# SMPS_power_supply.net
KiCad netlist of a schematic drawn in Altium Designer
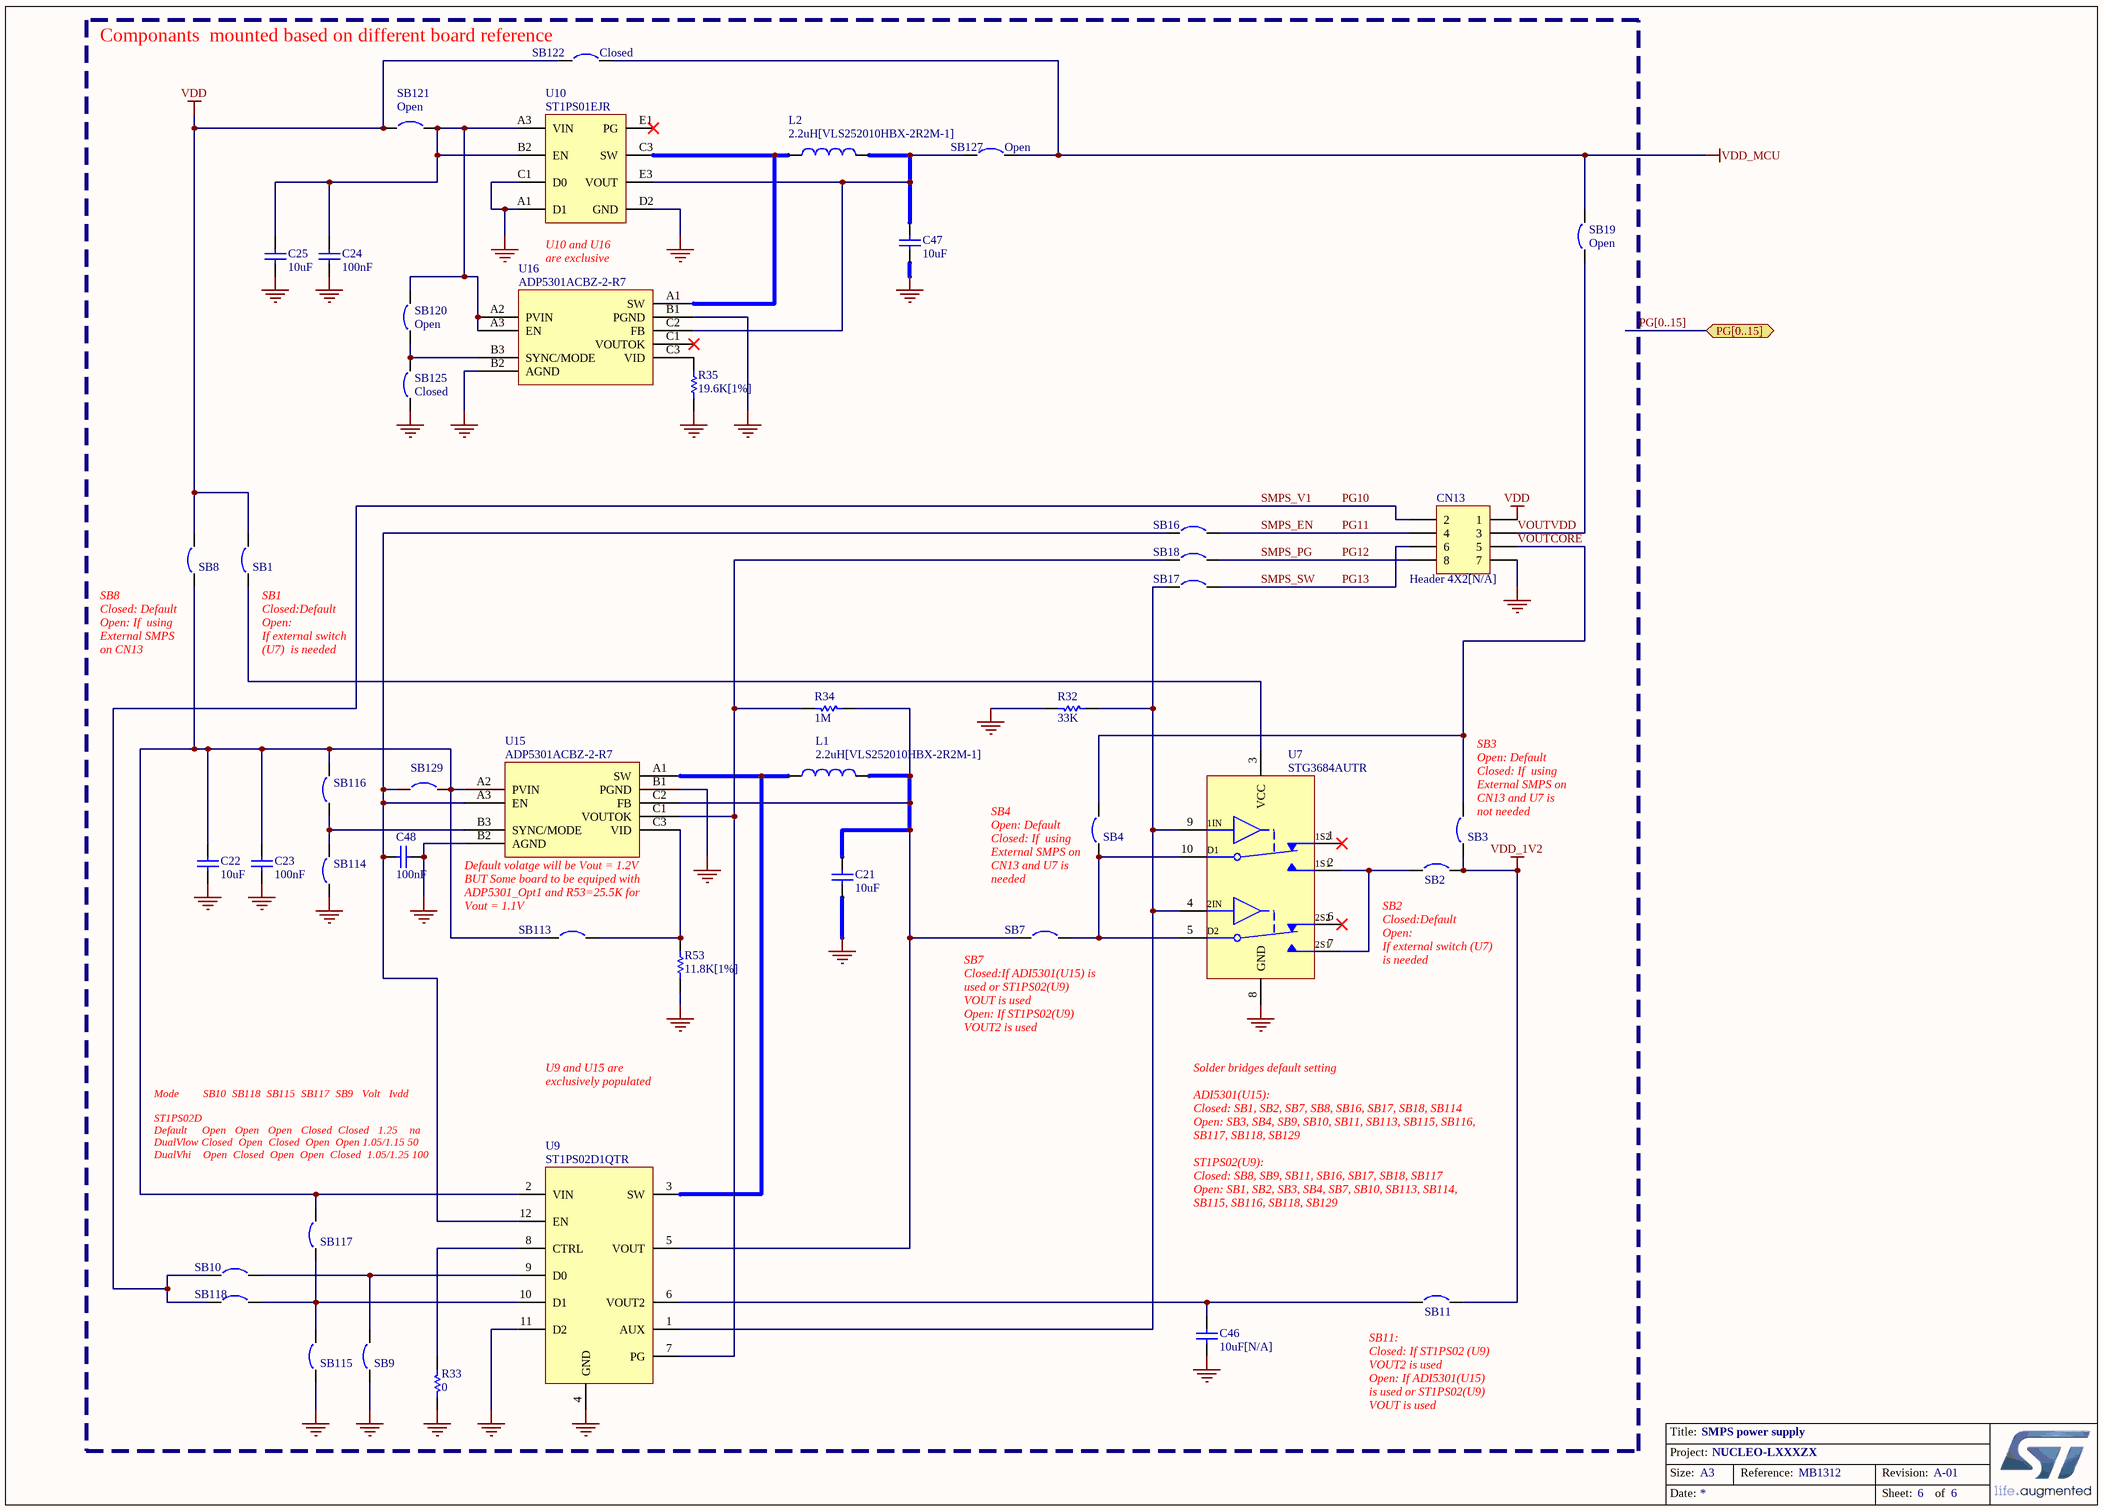
[diagram p0: SMPS power supply.SchDoc]

(export (version "E")
  (design (tool "Eeschema 10.0.6"))
  (components
    (comp (ref "C21")
      (value "10uF")
      (footprint "0603C")
      (description "Capacitor")
      (fields (field (name "PUBLISHER") "Altium Limited"))
      (libsource (lib "Miscellaneous Devices") (part "Cap"))
    )
    (comp (ref "C22")
      (value "10uF")
      (footprint "0603C")
      (description "Capacitor")
      (fields (field (name "PUBLISHER") "Altium Limited"))
      (libsource (lib "Miscellaneous Devices") (part "Cap"))
    )
    (comp (ref "C23")
      (value "100nF")
      (footprint "0603C")
      (description "Capacitor SMD 0603 100000pF X7R 50V +/-10%")
      (fields (field (name "MANUFACTURER") "YAGEO") (field (name "TOLERANCE") "10%"))
      (libsource (lib "NewComponents") (part "CAP_CC0603KRX7R9BB104"))
    )
    (comp (ref "C24")
      (value "100nF")
      (footprint "0603C")
      (description "Capacitor SMD 0603 100000pF X7R 50V +/-10%")
      (fields (field (name "MANUFACTURER") "YAGEO") (field (name "TOLERANCE") "10%"))
      (libsource (lib "NewComponents") (part "CAP_CC0603KRX7R9BB104"))
    )
    (comp (ref "C25")
      (value "10uF")
      (footprint "0603C")
      (description "Capacitor")
      (fields (field (name "PUBLISHER") "Altium Limited"))
      (libsource (lib "Miscellaneous Devices") (part "Cap"))
    )
    (comp (ref "C46")
      (value "10uF[N/A]")
      (footprint "0603C")
      (description "Capacitor")
      (fields (field (name "PUBLISHER") "Altium Limited"))
      (libsource (lib "Miscellaneous Devices") (part "Cap"))
    )
    (comp (ref "C47")
      (value "10uF")
      (footprint "0603C")
      (description "Capacitor")
      (fields (field (name "PUBLISHER") "Altium Limited"))
      (libsource (lib "Miscellaneous Devices") (part "Cap"))
    )
    (comp (ref "C48")
      (value "100nF")
      (footprint "0603C")
      (description "Capacitor SMD 0603 100000pF X7R 50V +/-10%")
      (fields (field (name "MANUFACTURER") "YAGEO") (field (name "TOLERANCE") "10%"))
      (libsource (lib "NewComponents") (part "CAP_CC0603KRX7R9BB104"))
    )
    (comp (ref "CN13")
      (value "Header 4X2[N/A]")
      (footprint "HDR_4x2_2R54_V_M")
      (description "Header, 4-Pin, Dual row")
      (fields (field (name "PUBLISHER") "Altium Limited"))
      (libsource (lib "MB1312") (part "Header 4X2_CN"))
    )
    (comp (ref "L1")
      (value "2.2uH[VLS252010HBX-2R2M-1]")
      (footprint "L1008_L0805_CPT")
      (description "Inductor")
      (fields (field (name "PUBLISHER") "Altium Limited"))
      (libsource (lib "Miscellaneous Devices") (part "Inductor"))
    )
    (comp (ref "L2")
      (value "2.2uH[VLS252010HBX-2R2M-1]")
      (footprint "L1008_L0805_CPT")
      (description "Inductor")
      (fields (field (name "PUBLISHER") "Altium Limited"))
      (libsource (lib "Miscellaneous Devices") (part "Inductor"))
    )
    (comp (ref "R32")
      (value "33K")
      (footprint "0603R")
      (description "Resistor")
      (fields (field (name "PUBLISHER") "Altium Limited"))
      (libsource (lib "Miscellaneous Devices") (part "Res1"))
    )
    (comp (ref "R33")
      (value "0")
      (footprint "0603R")
      (description "Resistor")
      (fields (field (name "PUBLISHER") "Altium Limited"))
      (libsource (lib "") (part "Res1_1"))
    )
    (comp (ref "R34")
      (value "1M")
      (footprint "0603R")
      (description "Resistor")
      (fields (field (name "PUBLISHER") "Altium Limited"))
      (libsource (lib "Miscellaneous Devices") (part "Res1"))
    )
    (comp (ref "R35")
      (value "19.6K[1%]")
      (footprint "0603R")
      (description "Resistor")
      (fields (field (name "PUBLISHER") "Altium Limited"))
      (libsource (lib "Miscellaneous Devices") (part "res1"))
    )
    (comp (ref "R53")
      (value "11.8K[1%]")
      (footprint "0603R")
      (description "Resistor")
      (fields (field (name "PUBLISHER") "Altium Limited"))
      (libsource (lib "Miscellaneous Devices") (part "res1"))
    )
    (comp (ref "SB1")
      (value "Circuit Breaker")
      (footprint "SB_0603")
      (fields (field (name "PUBLISHER") "Altium Limited"))
      (libsource (lib "MCD_TOOLS") (part "Circuit Breaker"))
    )
    (comp (ref "SB2")
      (value "Circuit Breaker")
      (footprint "SB_0603")
      (fields (field (name "PUBLISHER") "Altium Limited"))
      (libsource (lib "MCD_TOOLS") (part "Circuit Breaker"))
    )
    (comp (ref "SB3")
      (value "Circuit Breaker")
      (footprint "SB_0603")
      (fields (field (name "PUBLISHER") "Altium Limited"))
      (libsource (lib "MCD_TOOLS") (part "Circuit Breaker"))
    )
    (comp (ref "SB4")
      (value "Circuit Breaker")
      (footprint "SB_0603")
      (fields (field (name "PUBLISHER") "Altium Limited"))
      (libsource (lib "MCD_TOOLS") (part "Circuit Breaker"))
    )
    (comp (ref "SB7")
      (value "Circuit Breaker")
      (footprint "SB_0603")
      (fields (field (name "PUBLISHER") "Altium Limited"))
      (libsource (lib "MCD_TOOLS") (part "Circuit Breaker"))
    )
    (comp (ref "SB8")
      (value "Circuit Breaker")
      (footprint "SB_0603")
      (fields (field (name "PUBLISHER") "Altium Limited"))
      (libsource (lib "MCD_TOOLS") (part "Circuit Breaker"))
    )
    (comp (ref "SB9")
      (value "Circuit Breaker")
      (footprint "SB_0603")
      (fields (field (name "PUBLISHER") "Altium Limited"))
      (libsource (lib "MCD_TOOLS") (part "Circuit Breaker"))
    )
    (comp (ref "SB10")
      (value "Circuit Breaker")
      (footprint "SB_0603")
      (fields (field (name "PUBLISHER") "Altium Limited"))
      (libsource (lib "MCD_TOOLS") (part "Circuit Breaker"))
    )
    (comp (ref "SB11")
      (value "Circuit Breaker")
      (footprint "SB_0603")
      (fields (field (name "PUBLISHER") "Altium Limited"))
      (libsource (lib "MCD_TOOLS") (part "Circuit Breaker"))
    )
    (comp (ref "SB16")
      (value "Circuit Breaker")
      (footprint "SB_0603")
      (fields (field (name "PUBLISHER") "Altium Limited"))
      (libsource (lib "MCD_TOOLS") (part "Circuit Breaker"))
    )
    (comp (ref "SB17")
      (value "Circuit Breaker")
      (footprint "SB_0603")
      (fields (field (name "PUBLISHER") "Altium Limited"))
      (libsource (lib "MCD_TOOLS") (part "Circuit Breaker"))
    )
    (comp (ref "SB18")
      (value "Circuit Breaker")
      (footprint "SB_0603")
      (fields (field (name "PUBLISHER") "Altium Limited"))
      (libsource (lib "MCD_TOOLS") (part "Circuit Breaker"))
    )
    (comp (ref "SB19")
      (value "Open")
      (footprint "SB_0603")
      (description "Circuit Breaker")
      (fields (field (name "PUBLISHER") "Altium Limited"))
      (libsource (lib "MB1167") (part "Circuit Breaker"))
    )
    (comp (ref "SB113")
      (value "Open")
      (footprint "SB_0603")
      (description "Circuit Breaker")
      (fields (field (name "PUBLISHER") "Altium Limited"))
      (libsource (lib "MB1167") (part "Circuit Breaker"))
    )
    (comp (ref "SB114")
      (value "Closed")
      (footprint "SB_0603")
      (description "Circuit Breaker")
      (fields (field (name "PUBLISHER") "Altium Limited"))
      (libsource (lib "MB1167") (part "Circuit Breaker_close"))
    )
    (comp (ref "SB115")
      (value "Circuit Breaker")
      (footprint "SB_0603")
      (fields (field (name "PUBLISHER") "Altium Limited"))
      (libsource (lib "MCD_TOOLS") (part "Circuit Breaker"))
    )
    (comp (ref "SB116")
      (value "Open")
      (footprint "SB_0603")
      (description "Circuit Breaker")
      (fields (field (name "PUBLISHER") "Altium Limited"))
      (libsource (lib "MB1167") (part "Circuit Breaker"))
    )
    (comp (ref "SB117")
      (value "Circuit Breaker")
      (footprint "SB_0603")
      (fields (field (name "PUBLISHER") "Altium Limited"))
      (libsource (lib "MCD_TOOLS") (part "Circuit Breaker"))
    )
    (comp (ref "SB118")
      (value "Circuit Breaker")
      (footprint "SB_0603")
      (fields (field (name "PUBLISHER") "Altium Limited"))
      (libsource (lib "MCD_TOOLS") (part "Circuit Breaker"))
    )
    (comp (ref "SB120")
      (value "Open")
      (footprint "SB_0603")
      (description "Circuit Breaker")
      (fields (field (name "PUBLISHER") "Altium Limited"))
      (libsource (lib "MB1167") (part "Circuit Breaker"))
    )
    (comp (ref "SB121")
      (value "Open")
      (footprint "SB_0603")
      (description "Circuit Breaker")
      (fields (field (name "PUBLISHER") "Altium Limited"))
      (libsource (lib "MB1167") (part "Circuit Breaker"))
    )
    (comp (ref "SB122")
      (value "Closed")
      (footprint "SB_0603")
      (description "Circuit Breaker")
      (fields (field (name "PUBLISHER") "Altium Limited"))
      (libsource (lib "MB1167") (part "Circuit Breaker_close"))
    )
    (comp (ref "SB125")
      (value "Closed")
      (footprint "SB_0603")
      (description "Circuit Breaker")
      (fields (field (name "PUBLISHER") "Altium Limited"))
      (libsource (lib "MB1167") (part "Circuit Breaker_close"))
    )
    (comp (ref "SB127")
      (value "Open")
      (footprint "SB_0603")
      (description "Circuit Breaker")
      (fields (field (name "PUBLISHER") "Altium Limited"))
      (libsource (lib "MB1167") (part "Circuit Breaker"))
    )
    (comp (ref "SB129")
      (value "Open")
      (footprint "SB_0603")
      (description "Circuit Breaker")
      (fields (field (name "PUBLISHER") "Altium Limited"))
      (libsource (lib "MB1167") (part "Circuit Breaker"))
    )
    (comp (ref "U7")
      (value "STG3684AUTR")
      (footprint "QFN40P180X140X55-10N")
      (description "Low voltage 0.5 O max dual SPDT switch with break-before-make")
      (fields (field (name "MANUFACTURER") "ST"))
      (libsource (lib "NewComponents") (part "STG3684AUTR"))
    )
    (comp (ref "U9")
      (value "ST1PS02D1QTR")
      (footprint "QFN0P170X200X55-12N")
      (fields (field (name "MANUFACTURER") "STMicroelectronics"))
      (libsource (lib "NewComponents") (part "ST1PS022D1QTR"))
    )
    (comp (ref "U10")
      (value "ST1PS01EJR")
      (footprint "Flipchip8")
      (description "400mA Nano-Quiescent?Synchronous step-down converter  with voltage selection and power good")
      (fields (field (name "MANUFACTURER") "STMicroelectronics"))
      (libsource (lib "NewComponents") (part "ST1PS01FJR"))
    )
    (comp (ref "U15")
      (value "ADP5301ACBZ-2-R7")
      (footprint "WLCSP-9ball")
      (description "UL Step down regulator")
      (libsource (lib "Schlib1") (part "ADP5301"))
    )
    (comp (ref "U16")
      (value "ADP5301ACBZ-2-R7")
      (footprint "WLCSP-9ball")
      (description "UL Step down regulator")
      (libsource (lib "Schlib1") (part "ADP5301"))
    )
  )
  (nets
    (net (code "13") (name "/PG10") (class "Default")
      (node (ref "CN13") (pin "2") (pinfunction "2_2") (pintype "passive"))
      (node (ref "SB10") (pin "1") (pinfunction "1_1") (pintype "passive"))
      (node (ref "SB118") (pin "1") (pinfunction "1_1") (pintype "passive"))
    )
    (net (code "14") (name "/PG11") (class "Default")
      (node (ref "CN13") (pin "4") (pinfunction "4_4") (pintype "passive"))
      (node (ref "SB16") (pin "2") (pinfunction "2_2") (pintype "passive"))
    )
    (net (code "15") (name "/PG12") (class "Default")
      (node (ref "CN13") (pin "8") (pinfunction "8_8") (pintype "passive"))
      (node (ref "SB18") (pin "2") (pinfunction "2_2") (pintype "passive"))
    )
    (net (code "16") (name "/PG13") (class "Default")
      (node (ref "CN13") (pin "6") (pinfunction "6_6") (pintype "passive"))
      (node (ref "SB17") (pin "2") (pinfunction "2_2") (pintype "passive"))
    )
    (net (code "18") (name "/VOUTCORE") (class "Default")
      (node (ref "CN13") (pin "5") (pinfunction "5_5") (pintype "passive"))
      (node (ref "SB3") (pin "2") (pinfunction "2_2") (pintype "passive"))
      (node (ref "SB4") (pin "2") (pinfunction "2_2") (pintype "passive"))
    )
    (net (code "19") (name "/VOUTVDD") (class "Default")
      (node (ref "CN13") (pin "3") (pinfunction "3_3") (pintype "passive"))
      (node (ref "SB19") (pin "1") (pinfunction "1_1") (pintype "passive"))
    )
    (net (code "20") (name "GND") (class "Default")
      (node (ref "C21") (pin "1") (pinfunction "1_1") (pintype "passive"))
      (node (ref "C22") (pin "1") (pinfunction "1_1") (pintype "passive"))
      (node (ref "C23") (pin "2") (pinfunction "2_2") (pintype "passive"))
      (node (ref "C24") (pin "2") (pinfunction "2_2") (pintype "passive"))
      (node (ref "C25") (pin "1") (pinfunction "1_1") (pintype "passive"))
      (node (ref "C46") (pin "1") (pinfunction "1_1") (pintype "passive"))
      (node (ref "C47") (pin "1") (pinfunction "1_1") (pintype "passive"))
      (node (ref "C48") (pin "2") (pinfunction "2_2") (pintype "passive"))
      (node (ref "CN13") (pin "7") (pinfunction "7_7") (pintype "passive"))
      (node (ref "R32") (pin "2") (pinfunction "2_2") (pintype "passive"))
      (node (ref "R33") (pin "1") (pinfunction "1_1") (pintype "passive"))
      (node (ref "R35") (pin "1") (pinfunction "1_1") (pintype "passive"))
      (node (ref "R53") (pin "1") (pinfunction "1_1") (pintype "passive"))
      (node (ref "SB114") (pin "1") (pinfunction "1_1") (pintype "passive"))
      (node (ref "SB115") (pin "1") (pinfunction "1_1") (pintype "passive"))
      (node (ref "SB125") (pin "1") (pinfunction "1_1") (pintype "passive"))
      (node (ref "SB9") (pin "1") (pinfunction "1_1") (pintype "passive"))
      (node (ref "U10") (pin "A1") (pinfunction "D1_A1") (pintype "passive"))
      (node (ref "U10") (pin "C1") (pinfunction "D0_C1") (pintype "passive"))
      (node (ref "U10") (pin "D2") (pinfunction "GND_D2") (pintype "passive"))
      (node (ref "U15") (pin "B1") (pinfunction "PGND_B1") (pintype "passive"))
      (node (ref "U15") (pin "B2") (pinfunction "AGND_B2") (pintype "passive"))
      (node (ref "U16") (pin "B1") (pinfunction "PGND_B1") (pintype "passive"))
      (node (ref "U16") (pin "B2") (pinfunction "AGND_B2") (pintype "passive"))
      (node (ref "U7") (pin "8") (pinfunction "GND_8") (pintype "passive"))
      (node (ref "U9") (pin "11") (pinfunction "D2_11") (pintype "passive"))
      (node (ref "U9") (pin "4") (pinfunction "GND_4") (pintype "passive"))
    )
    (net (code "21") (name "Net-(U7-1IN)") (class "Default")
      (node (ref "R32") (pin "1") (pinfunction "1_1") (pintype "passive"))
      (node (ref "SB17") (pin "1") (pinfunction "1_1") (pintype "passive"))
      (node (ref "U7") (pin "4") (pinfunction "2IN_4") (pintype "passive"))
      (node (ref "U7") (pin "9") (pinfunction "1IN_9") (pintype "passive"))
      (node (ref "U9") (pin "1") (pinfunction "AUX_1") (pintype "passive"))
    )
    (net (code "22") (name "Net-(U7-1S1)") (class "Default")
      (node (ref "SB2") (pin "1") (pinfunction "1_1") (pintype "passive"))
      (node (ref "U7") (pin "2") (pinfunction "1S1_2") (pintype "passive"))
      (node (ref "U7") (pin "7") (pinfunction "2S1_7") (pintype "passive"))
    )
    (net (code "23") (name "Net-(U7-D1)") (class "Default")
      (node (ref "SB4") (pin "1") (pinfunction "1_1") (pintype "passive"))
      (node (ref "SB7") (pin "2") (pinfunction "2_2") (pintype "passive"))
      (node (ref "U7") (pin "10") (pinfunction "D1_10") (pintype "passive"))
      (node (ref "U7") (pin "5") (pinfunction "D2_5") (pintype "passive"))
    )
    (net (code "24") (name "Net-(U7-VCC)") (class "Default")
      (node (ref "SB1") (pin "1") (pinfunction "1_1") (pintype "passive"))
      (node (ref "U7") (pin "3") (pinfunction "VCC_3") (pintype "passive"))
    )
    (net (code "25") (name "Net-(U9-CTRL)") (class "Default")
      (node (ref "R33") (pin "2") (pinfunction "2_2") (pintype "passive"))
      (node (ref "U9") (pin "8") (pinfunction "CTRL_8") (pintype "passive"))
    )
    (net (code "26") (name "Net-(U9-D0)") (class "Default")
      (node (ref "SB10") (pin "2") (pinfunction "2_2") (pintype "passive"))
      (node (ref "SB9") (pin "2") (pinfunction "2_2") (pintype "passive"))
      (node (ref "U9") (pin "9") (pinfunction "D0_9") (pintype "passive"))
    )
    (net (code "27") (name "Net-(U9-D1)") (class "Default")
      (node (ref "SB115") (pin "2") (pinfunction "2_2") (pintype "passive"))
      (node (ref "SB117") (pin "1") (pinfunction "1_1") (pintype "passive"))
      (node (ref "SB118") (pin "2") (pinfunction "2_2") (pintype "passive"))
      (node (ref "U9") (pin "10") (pinfunction "D1_10") (pintype "passive"))
    )
    (net (code "28") (name "Net-(U9-VOUT2)") (class "Default")
      (node (ref "C46") (pin "2") (pinfunction "2_2") (pintype "passive"))
      (node (ref "SB11") (pin "1") (pinfunction "1_1") (pintype "passive"))
      (node (ref "U9") (pin "6") (pinfunction "VOUT2_6") (pintype "passive"))
    )
    (net (code "29") (name "Net-(U10-EN)") (class "Default")
      (node (ref "C24") (pin "1") (pinfunction "1_1") (pintype "passive"))
      (node (ref "C25") (pin "2") (pinfunction "2_2") (pintype "passive"))
      (node (ref "SB120") (pin "2") (pinfunction "2_2") (pintype "passive"))
      (node (ref "SB121") (pin "2") (pinfunction "2_2") (pintype "passive"))
      (node (ref "U10") (pin "A3") (pinfunction "VIN_A3") (pintype "passive"))
      (node (ref "U10") (pin "B2") (pinfunction "EN_B2") (pintype "passive"))
      (node (ref "U16") (pin "A2") (pinfunction "PVIN_A2") (pintype "passive"))
      (node (ref "U16") (pin "A3") (pinfunction "EN_A3") (pintype "passive"))
    )
    (net (code "30") (name "Net-(U10-SW)") (class "Default")
      (node (ref "L2") (pin "1") (pinfunction "1_1") (pintype "passive"))
      (node (ref "U10") (pin "C3") (pinfunction "SW_C3") (pintype "passive"))
      (node (ref "U16") (pin "A1") (pinfunction "SW_A1") (pintype "passive"))
    )
    (net (code "31") (name "Net-(U10-VOUT)") (class "Default")
      (node (ref "C47") (pin "2") (pinfunction "2_2") (pintype "passive"))
      (node (ref "L2") (pin "2") (pinfunction "2_2") (pintype "passive"))
      (node (ref "SB127") (pin "1") (pinfunction "1_1") (pintype "passive"))
      (node (ref "U10") (pin "E3") (pinfunction "VOUT_E3") (pintype "passive"))
      (node (ref "U16") (pin "C2") (pinfunction "FB_C2") (pintype "passive"))
    )
    (net (code "32") (name "Net-(U15-EN)") (class "Default")
      (node (ref "C48") (pin "1") (pinfunction "1_1") (pintype "passive"))
      (node (ref "SB129") (pin "1") (pinfunction "1_1") (pintype "passive"))
      (node (ref "SB16") (pin "1") (pinfunction "1_1") (pintype "passive"))
      (node (ref "U15") (pin "A3") (pinfunction "EN_A3") (pintype "passive"))
      (node (ref "U9") (pin "12") (pinfunction "EN_12") (pintype "passive"))
    )
    (net (code "33") (name "Net-(U15-FB)") (class "Default")
      (node (ref "C21") (pin "2") (pinfunction "2_2") (pintype "passive"))
      (node (ref "L1") (pin "2") (pinfunction "2_2") (pintype "passive"))
      (node (ref "R34") (pin "1") (pinfunction "1_1") (pintype "passive"))
      (node (ref "SB7") (pin "1") (pinfunction "1_1") (pintype "passive"))
      (node (ref "U15") (pin "C2") (pinfunction "FB_C2") (pintype "passive"))
      (node (ref "U9") (pin "5") (pinfunction "VOUT_5") (pintype "passive"))
    )
    (net (code "34") (name "Net-(U15-PVIN)") (class "Default")
      (node (ref "C22") (pin "2") (pinfunction "2_2") (pintype "passive"))
      (node (ref "C23") (pin "1") (pinfunction "1_1") (pintype "passive"))
      (node (ref "SB113") (pin "1") (pinfunction "1_1") (pintype "passive"))
      (node (ref "SB116") (pin "2") (pinfunction "2_2") (pintype "passive"))
      (node (ref "SB117") (pin "2") (pinfunction "2_2") (pintype "passive"))
      (node (ref "SB129") (pin "2") (pinfunction "2_2") (pintype "passive"))
      (node (ref "SB8") (pin "1") (pinfunction "1_1") (pintype "passive"))
      (node (ref "U15") (pin "A2") (pinfunction "PVIN_A2") (pintype "passive"))
      (node (ref "U9") (pin "2") (pinfunction "VIN_2") (pintype "passive"))
    )
    (net (code "35") (name "Net-(U15-SW)") (class "Default")
      (node (ref "L1") (pin "1") (pinfunction "1_1") (pintype "passive"))
      (node (ref "U15") (pin "A1") (pinfunction "SW_A1") (pintype "passive"))
      (node (ref "U9") (pin "3") (pinfunction "SW_3") (pintype "passive"))
    )
    (net (code "36") (name "Net-(U15-SYNC{slash}MODE)") (class "Default")
      (node (ref "SB114") (pin "2") (pinfunction "2_2") (pintype "passive"))
      (node (ref "SB116") (pin "1") (pinfunction "1_1") (pintype "passive"))
      (node (ref "U15") (pin "B3") (pinfunction "SYNC/MODE_B3") (pintype "passive"))
    )
    (net (code "37") (name "Net-(U15-VID)") (class "Default")
      (node (ref "R53") (pin "2") (pinfunction "2_2") (pintype "passive"))
      (node (ref "SB113") (pin "2") (pinfunction "2_2") (pintype "passive"))
      (node (ref "U15") (pin "C3") (pinfunction "VID_C3") (pintype "passive"))
    )
    (net (code "38") (name "Net-(U15-VOUTOK)") (class "Default")
      (node (ref "R34") (pin "2") (pinfunction "2_2") (pintype "passive"))
      (node (ref "SB18") (pin "1") (pinfunction "1_1") (pintype "passive"))
      (node (ref "U15") (pin "C1") (pinfunction "VOUTOK_C1") (pintype "passive"))
      (node (ref "U9") (pin "7") (pinfunction "PG_7") (pintype "passive"))
    )
    (net (code "39") (name "Net-(U16-SYNC{slash}MODE)") (class "Default")
      (node (ref "SB120") (pin "1") (pinfunction "1_1") (pintype "passive"))
      (node (ref "SB125") (pin "2") (pinfunction "2_2") (pintype "passive"))
      (node (ref "U16") (pin "B3") (pinfunction "SYNC/MODE_B3") (pintype "passive"))
    )
    (net (code "40") (name "Net-(U16-VID)") (class "Default")
      (node (ref "R35") (pin "2") (pinfunction "2_2") (pintype "passive"))
      (node (ref "U16") (pin "C3") (pinfunction "VID_C3") (pintype "passive"))
    )
    (net (code "41") (name "VDD") (class "Default")
      (node (ref "CN13") (pin "1") (pinfunction "1_1") (pintype "passive"))
      (node (ref "SB1") (pin "2") (pinfunction "2_2") (pintype "passive"))
      (node (ref "SB121") (pin "1") (pinfunction "1_1") (pintype "passive"))
      (node (ref "SB122") (pin "1") (pinfunction "1_1") (pintype "passive"))
      (node (ref "SB8") (pin "2") (pinfunction "2_2") (pintype "passive"))
    )
    (net (code "42") (name "VDD_1V2") (class "Default")
      (node (ref "SB11") (pin "2") (pinfunction "2_2") (pintype "passive"))
      (node (ref "SB2") (pin "2") (pinfunction "2_2") (pintype "passive"))
      (node (ref "SB3") (pin "1") (pinfunction "1_1") (pintype "passive"))
    )
    (net (code "43") (name "VDD_MCU") (class "Default")
      (node (ref "SB122") (pin "2") (pinfunction "2_2") (pintype "passive"))
      (node (ref "SB127") (pin "2") (pinfunction "2_2") (pintype "passive"))
      (node (ref "SB19") (pin "2") (pinfunction "2_2") (pintype "passive"))
    )
    (net (code "44") (name "unconnected-(U7-1S2-Pad1)") (class "Default")
      (node (ref "U7") (pin "1") (pinfunction "1S2_1") (pintype "passive+no_connect"))
    )
    (net (code "45") (name "unconnected-(U7-2S2-Pad6)") (class "Default")
      (node (ref "U7") (pin "6") (pinfunction "2S2_6") (pintype "passive+no_connect"))
    )
    (net (code "46") (name "unconnected-(U10-PG-PadE1)") (class "Default")
      (node (ref "U10") (pin "E1") (pinfunction "PG_E1") (pintype "passive+no_connect"))
    )
    (net (code "47") (name "unconnected-(U16-VOUTOK-PadC1)") (class "Default")
      (node (ref "U16") (pin "C1") (pinfunction "VOUTOK_C1") (pintype "passive+no_connect"))
    )
  )
)
